# 07_CAN.net
KiCad netlist of a schematic drawn in Altium Designer
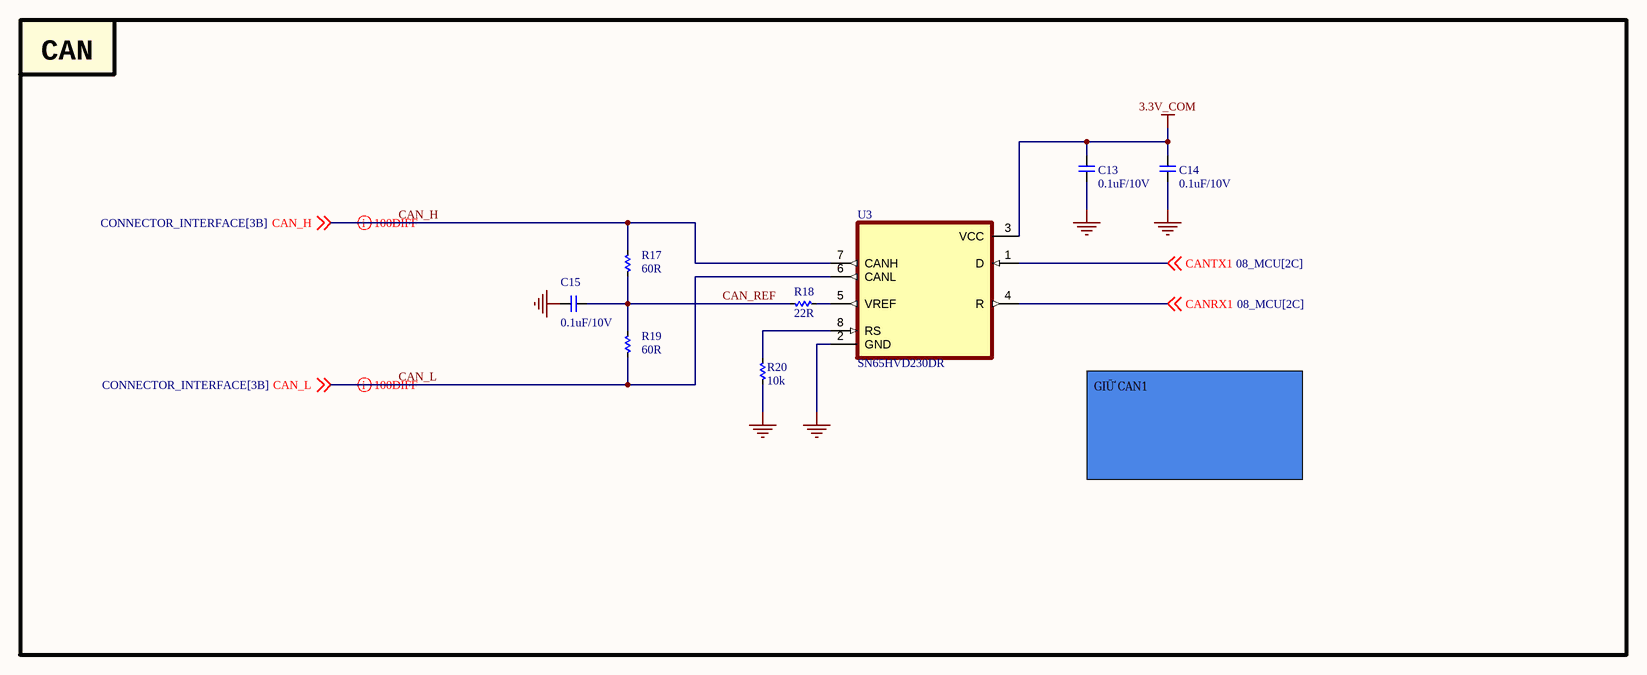
[diagram p0: 07_CAN.SchDoc]

(export (version "E")
  (design (tool "Eeschema 10.0.6"))
  (components
    (comp (ref "C13")
      (value "0.1uF/10V")
      (footprint "CAP_C_1005X50_L")
      (description "CAP")
      (libsource (lib "LABLIB") (part "_CAP_C_2"))
    )
    (comp (ref "C14")
      (value "0.1uF/10V")
      (footprint "CAP_C_1005X50_L")
      (description "CAP")
      (libsource (lib "LABLIB") (part "_CAP_C_2"))
    )
    (comp (ref "C15")
      (value "0.1uF/10V")
      (footprint "CAP_C_1005X50_L")
      (description "CAP")
      (libsource (lib "LABLIB") (part "_CAP_C_2"))
    )
    (comp (ref "R17")
      (value "60R")
      (footprint "RES_C_1005X40")
      (description "RES")
      (libsource (lib "LABLIB") (part "_RES_B_2"))
    )
    (comp (ref "R18")
      (value "22R")
      (footprint "RES_C_1005X40")
      (description "RES")
      (libsource (lib "LABLIB") (part "_RES_B_2"))
    )
    (comp (ref "R19")
      (value "60R")
      (footprint "RES_C_1005X40")
      (description "RES")
      (libsource (lib "LABLIB") (part "_RES_B_2"))
    )
    (comp (ref "R20")
      (value "10k")
      (footprint "RES_C_1005X40")
      (description "RES")
      (libsource (lib "LABLIB") (part "_RES_B_2"))
    )
    (comp (ref "U3")
      (value "SN65HVD230DR")
      (footprint "SOIC127P600X175-8N")
      (description "3.3 V CAN Transceiver with Standby Mode")
      (fields (field (name "MF") "Texas Instruments"))
      (libsource (lib "BEE-1012 PAY-EXP_V110") (part "SN65HVD230DR"))
    )
  )
  (nets
    (net (code "1") (name "/CAN_REF") (class "Default")
      (node (ref "C15") (pin "1") (pinfunction "1_1") (pintype "passive"))
      (node (ref "R17") (pin "1") (pinfunction "1_1") (pintype "passive"))
      (node (ref "R18") (pin "1") (pinfunction "1_1") (pintype "passive"))
      (node (ref "R19") (pin "2") (pinfunction "2_2") (pintype "passive"))
    )
    (net (code "2") (name "3.3V_COM") (class "Default")
      (node (ref "C13") (pin "1") (pinfunction "1_1") (pintype "passive"))
      (node (ref "C14") (pin "1") (pinfunction "1_1") (pintype "passive"))
      (node (ref "U3") (pin "3") (pinfunction "VCC_3") (pintype "power_in"))
    )
    (net (code "3") (name "CANRX1") (class "Default")
      (node (ref "U3") (pin "4") (pinfunction "R_4") (pintype "output"))
    )
    (net (code "4") (name "CANTX1") (class "Default")
      (node (ref "U3") (pin "1") (pinfunction "D_1") (pintype "input"))
    )
    (net (code "5") (name "CAN_H") (class "Default")
      (node (ref "R17") (pin "2") (pinfunction "2_2") (pintype "passive"))
      (node (ref "U3") (pin "7") (pinfunction "CANH_7") (pintype "output"))
    )
    (net (code "6") (name "CAN_L") (class "Default")
      (node (ref "R19") (pin "1") (pinfunction "1_1") (pintype "passive"))
      (node (ref "U3") (pin "6") (pinfunction "CANL_6") (pintype "output"))
    )
    (net (code "7") (name "GND") (class "Default")
      (node (ref "C13") (pin "2") (pinfunction "2_2") (pintype "passive"))
      (node (ref "C14") (pin "2") (pinfunction "2_2") (pintype "passive"))
      (node (ref "C15") (pin "2") (pinfunction "2_2") (pintype "passive"))
      (node (ref "R20") (pin "1") (pinfunction "1_1") (pintype "passive"))
      (node (ref "U3") (pin "2") (pinfunction "GND_2") (pintype "power_in"))
    )
    (net (code "8") (name "Net-(U3-RS)") (class "Default")
      (node (ref "R20") (pin "2") (pinfunction "2_2") (pintype "passive"))
      (node (ref "U3") (pin "8") (pinfunction "RS_8") (pintype "input"))
    )
    (net (code "9") (name "Net-(U3-VREF)") (class "Default")
      (node (ref "R18") (pin "2") (pinfunction "2_2") (pintype "passive"))
      (node (ref "U3") (pin "5") (pinfunction "VREF_5") (pintype "output"))
    )
  )
)
